# NFC_Card.net
KiCad netlist of a schematic drawn in EasyEDA Pro
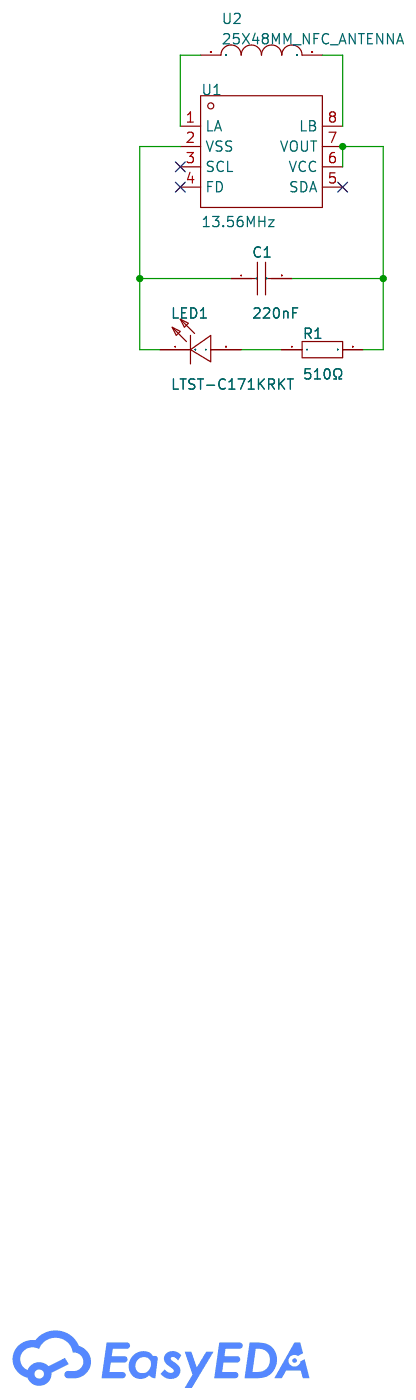
[diagram p0: schematic sheet]

(export (version "E")
  (design (tool "Eeschema 10.0.6"))
  (components
    (comp (ref "C1")
      (value "220nF")
      (footprint "easyedapro:C0603")
      (description "容值:220nF;精度:±10%;额定电压:25V;材质(温度系数):X7R;")
      (fields
        (field (name "Manufacturer Part") "CL10B224KA8NNNC")
        (field (name "Manufacturer") "SAMSUNG(三星)")
      )
      (libsource (lib "easyedapro") (part "CL10B224KA8NNNC"))
    )
    (comp (ref "LED1")
      (value "LTST-C171KRKT")
      (footprint "easyedapro:LED-SMD_L2.0-W1.25-RD_RED")
      (fields (field (name "Manufacturer") "LITEON(光宝)"))
      (libsource (lib "easyedapro") (part "LTST-C171KRKT"))
    )
    (comp (ref "R1")
      (value "510Ω")
      (footprint "easyedapro:R0402")
      (fields (field (name "Manufacturer Part") "RC0402FR-07510RL") (field (name "Manufacturer") "YAGEO(国巨)"))
      (libsource (lib "easyedapro") (part "RC0402FR-07510RL"))
    )
    (comp (ref "U1")
      (value "13.56MHz")
      (footprint "easyedapro:XQFN-8_L1.6-W1.6-P0.50-BL_NT3H2111W0FHKH")
      (fields (field (name "Manufacturer Part") "NT3H2111W0FHKH") (field (name "Manufacturer") "NXP(恩智浦)"))
      (libsource (lib "easyedapro") (part "NT3H2111W0FHKH"))
    )
    (comp (ref "U2")
      (value "25X48MM_NFC_ANTENNA")
      (footprint "easyedapro:25X48MM_NFC_ANTENNA")
      (libsource (lib "easyedapro") (part "25X48MM_NFC_ANTENNA"))
    )
  )
  (nets
    (net (code "1") (name "Net-(LED1-A)") (class "Default")
      (node (ref "LED1") (pin "2") (pinfunction "A_2") (pintype "input"))
      (node (ref "R1") (pin "1") (pinfunction "1_1") (pintype "unspecified"))
    )
    (net (code "2") (name "Net-(LED1-C)") (class "Default")
      (node (ref "C1") (pin "1") (pinfunction "1_1") (pintype "input"))
      (node (ref "LED1") (pin "1") (pinfunction "C_1") (pintype "input"))
      (node (ref "U1") (pin "2") (pinfunction "VSS_2") (pintype "unspecified"))
    )
    (net (code "3") (name "Net-(U1-LA)") (class "Default")
      (node (ref "U1") (pin "1") (pinfunction "LA_1") (pintype "unspecified"))
      (node (ref "U2") (pin "P$1") (pinfunction "P$1_P$1") (pintype "bidirectional"))
    )
    (net (code "4") (name "Net-(U1-LB)") (class "Default")
      (node (ref "U1") (pin "8") (pinfunction "LB_8") (pintype "unspecified"))
      (node (ref "U2") (pin "P$2") (pinfunction "P$2_P$2") (pintype "bidirectional"))
    )
    (net (code "5") (name "Net-(U1-VCC)") (class "Default")
      (node (ref "C1") (pin "2") (pinfunction "2_2") (pintype "input"))
      (node (ref "R1") (pin "2") (pinfunction "2_2") (pintype "unspecified"))
      (node (ref "U1") (pin "6") (pinfunction "VCC_6") (pintype "unspecified"))
      (node (ref "U1") (pin "7") (pinfunction "VOUT_7") (pintype "unspecified"))
    )
    (net (code "6") (name "unconnected-(U1-FD-Pad4)") (class "Default")
      (node (ref "U1") (pin "4") (pinfunction "FD_4") (pintype "unspecified+no_connect"))
    )
    (net (code "7") (name "unconnected-(U1-SCL-Pad3)") (class "Default")
      (node (ref "U1") (pin "3") (pinfunction "SCL_3") (pintype "unspecified+no_connect"))
    )
    (net (code "8") (name "unconnected-(U1-SDA-Pad5)") (class "Default")
      (node (ref "U1") (pin "5") (pinfunction "SDA_5") (pintype "unspecified+no_connect"))
    )
  )
)
